# ltc.net
KiCad netlist of a schematic drawn in EAGLE
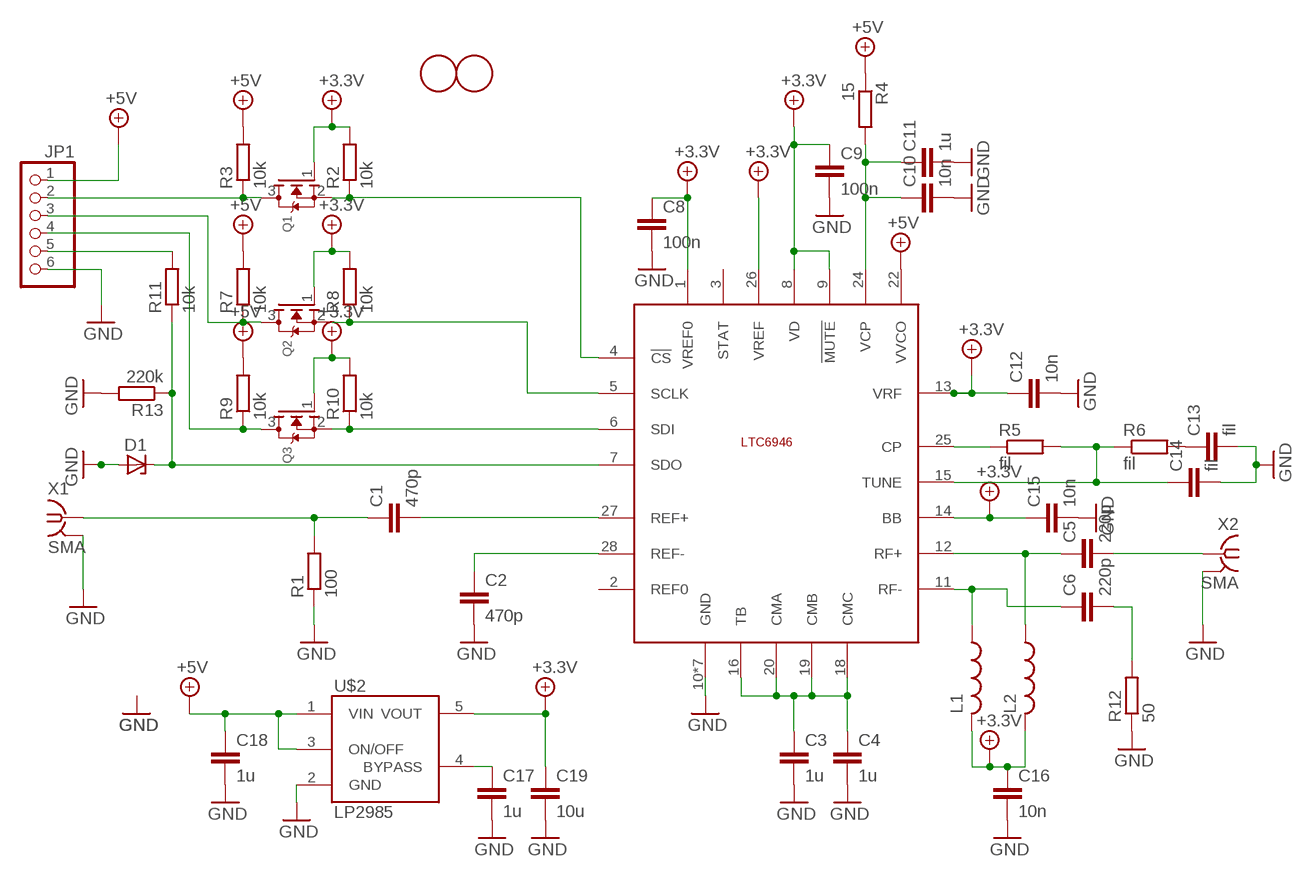
[diagram p0: schematic, sheet 1]

(export (version "E")
  (design (tool "Eeschema 10.0.6"))
  (components
    (comp (ref "C1")
      (value "470p")
      (footprint "eagle-import:C0603")
      (libsource (lib "eagle-import") (part "C-EUC0603"))
    )
    (comp (ref "C2")
      (value "470p")
      (footprint "eagle-import:C0603")
      (libsource (lib "eagle-import") (part "C-EUC0603"))
    )
    (comp (ref "C3")
      (value "1u")
      (footprint "eagle-import:C0603")
      (libsource (lib "eagle-import") (part "C-EUC0603"))
    )
    (comp (ref "C4")
      (value "1u")
      (footprint "eagle-import:C0603")
      (libsource (lib "eagle-import") (part "C-EUC0603"))
    )
    (comp (ref "C5")
      (value "220p")
      (footprint "eagle-import:C0603")
      (libsource (lib "eagle-import") (part "C-EUC0603"))
    )
    (comp (ref "C6")
      (value "220p")
      (footprint "eagle-import:C0603")
      (libsource (lib "eagle-import") (part "C-EUC0603"))
    )
    (comp (ref "C8")
      (value "100n")
      (footprint "eagle-import:C0603")
      (libsource (lib "eagle-import") (part "C-EUC0603"))
    )
    (comp (ref "C9")
      (value "100n")
      (footprint "eagle-import:C0603")
      (libsource (lib "eagle-import") (part "C-EUC0603"))
    )
    (comp (ref "C10")
      (value "10n")
      (footprint "eagle-import:C0603")
      (libsource (lib "eagle-import") (part "C-EUC0603"))
    )
    (comp (ref "C11")
      (value "1u")
      (footprint "eagle-import:C0603")
      (libsource (lib "eagle-import") (part "C-EUC0603"))
    )
    (comp (ref "C12")
      (value "10n")
      (footprint "eagle-import:C0603")
      (libsource (lib "eagle-import") (part "C-EUC0603"))
    )
    (comp (ref "C13")
      (value "fil")
      (footprint "eagle-import:C0603")
      (libsource (lib "eagle-import") (part "C-EUC0603"))
    )
    (comp (ref "C14")
      (value "fil")
      (footprint "eagle-import:C0603")
      (libsource (lib "eagle-import") (part "C-EUC0603"))
    )
    (comp (ref "C15")
      (value "10n")
      (footprint "eagle-import:C0603")
      (libsource (lib "eagle-import") (part "C-EUC0603"))
    )
    (comp (ref "C16")
      (value "10n")
      (footprint "eagle-import:C0603")
      (libsource (lib "eagle-import") (part "C-EUC0603"))
    )
    (comp (ref "C17")
      (value "1u")
      (footprint "eagle-import:C0603")
      (libsource (lib "eagle-import") (part "C-EUC0603"))
    )
    (comp (ref "C18")
      (value "1u")
      (footprint "eagle-import:C0603")
      (libsource (lib "eagle-import") (part "C-EUC0603"))
    )
    (comp (ref "C19")
      (value "10u")
      (footprint "eagle-import:C0603")
      (libsource (lib "eagle-import") (part "C-EUC0603"))
    )
    (comp (ref "D1")
      (value "ZENER-DIODESOT23")
      (footprint "eagle-import:SOT23")
      (libsource (lib "eagle-import") (part "ZENER-DIODESOT23"))
    )
    (comp (ref "JP1")
      (value "PINHD-1X6B")
      (footprint "eagle-import:1X06-BIG")
      (libsource (lib "eagle-import") (part "PINHD-1X6B"))
    )
    (comp (ref "L1")
      (value "L-USL2825P")
      (footprint "eagle-import:L2825P")
      (libsource (lib "eagle-import") (part "L-USL2825P"))
    )
    (comp (ref "L2")
      (value "L-USL2825P")
      (footprint "eagle-import:L2825P")
      (libsource (lib "eagle-import") (part "L-USL2825P"))
    )
    (comp (ref "Q1")
      (value "MOSFET-NREFLOW")
      (footprint "eagle-import:SOT23")
      (libsource (lib "eagle-import") (part "MOSFET-NREFLOW"))
    )
    (comp (ref "Q2")
      (value "MOSFET-NREFLOW")
      (footprint "eagle-import:SOT23")
      (libsource (lib "eagle-import") (part "MOSFET-NREFLOW"))
    )
    (comp (ref "Q3")
      (value "MOSFET-NREFLOW")
      (footprint "eagle-import:SOT23")
      (libsource (lib "eagle-import") (part "MOSFET-NREFLOW"))
    )
    (comp (ref "R1")
      (value "100")
      (footprint "eagle-import:R0603")
      (libsource (lib "eagle-import") (part "R-EU_R0603"))
    )
    (comp (ref "R2")
      (value "10k")
      (footprint "eagle-import:R0603")
      (libsource (lib "eagle-import") (part "R-EU_R0603"))
    )
    (comp (ref "R3")
      (value "10k")
      (footprint "eagle-import:R0603")
      (libsource (lib "eagle-import") (part "R-EU_R0603"))
    )
    (comp (ref "R4")
      (value "15")
      (footprint "eagle-import:R0603")
      (libsource (lib "eagle-import") (part "R-EU_R0603"))
    )
    (comp (ref "R5")
      (value "fil")
      (footprint "eagle-import:R0603")
      (libsource (lib "eagle-import") (part "R-EU_R0603"))
    )
    (comp (ref "R6")
      (value "fil")
      (footprint "eagle-import:R0603")
      (libsource (lib "eagle-import") (part "R-EU_R0603"))
    )
    (comp (ref "R7")
      (value "10k")
      (footprint "eagle-import:R0603")
      (libsource (lib "eagle-import") (part "R-EU_R0603"))
    )
    (comp (ref "R8")
      (value "10k")
      (footprint "eagle-import:R0603")
      (libsource (lib "eagle-import") (part "R-EU_R0603"))
    )
    (comp (ref "R9")
      (value "10k")
      (footprint "eagle-import:R0603")
      (libsource (lib "eagle-import") (part "R-EU_R0603"))
    )
    (comp (ref "R10")
      (value "10k")
      (footprint "eagle-import:R0603")
      (libsource (lib "eagle-import") (part "R-EU_R0603"))
    )
    (comp (ref "R11")
      (value "10k")
      (footprint "eagle-import:R0603")
      (libsource (lib "eagle-import") (part "R-EU_R0603"))
    )
    (comp (ref "R12")
      (value "50")
      (footprint "eagle-import:R0603")
      (libsource (lib "eagle-import") (part "R-EU_R0603"))
    )
    (comp (ref "R13")
      (value "220k")
      (footprint "eagle-import:R0603")
      (libsource (lib "eagle-import") (part "R-EU_R0603"))
    )
    (comp (ref "U$1")
      (value "LTC6946")
      (footprint "eagle-import:QFN28-UFD")
      (libsource (lib "eagle-import") (part "LTC6946"))
    )
    (comp (ref "U$2")
      (value "LP2985AIM5-3.3")
      (footprint "eagle-import:SOT25")
      (libsource (lib "eagle-import") (part "LP2985AIM5-3.3"))
    )
    (comp (ref "U$3")
      (value "FIDUCIAL")
      (footprint "eagle-import:FIDUCIAL_1MM")
      (libsource (lib "eagle-import") (part "FIDUCIAL"))
    )
    (comp (ref "U$4")
      (value "FIDUCIAL")
      (footprint "eagle-import:FIDUCIAL_1MM")
      (libsource (lib "eagle-import") (part "FIDUCIAL"))
    )
    (comp (ref "X1")
      (value "SMA")
      (footprint "eagle-import:J502-ND-142-0711-821_826")
      (fields (field (name "MF") "JOHNSON COMPONENTS") (field (name "MPN") "142-0711-821"))
      (libsource (lib "eagle-import") (part "SMA-142-0711-821/826"))
    )
    (comp (ref "X2")
      (value "SMA")
      (footprint "eagle-import:J502-ND-142-0711-821_826")
      (fields (field (name "MF") "JOHNSON COMPONENTS") (field (name "MPN") "142-0711-821"))
      (libsource (lib "eagle-import") (part "SMA-142-0711-821/826"))
    )
  )
  (nets
    (net (code "1") (name "+3.3V") (class "Default")
      (node (ref "C12") (pin "1") (pinfunction "1_1") (pintype "passive"))
      (node (ref "C15") (pin "1") (pinfunction "1_1") (pintype "passive"))
      (node (ref "C16") (pin "1") (pinfunction "1_1") (pintype "passive"))
      (node (ref "C19") (pin "1") (pinfunction "1_1") (pintype "passive"))
      (node (ref "C8") (pin "1") (pinfunction "1_1") (pintype "passive"))
      (node (ref "C9") (pin "1") (pinfunction "1_1") (pintype "passive"))
      (node (ref "L1") (pin "2") (pinfunction "2_2") (pintype "passive"))
      (node (ref "L2") (pin "2") (pinfunction "2_2") (pintype "passive"))
      (node (ref "Q1") (pin "1") (pinfunction "G_1") (pintype "bidirectional"))
      (node (ref "Q2") (pin "1") (pinfunction "G_1") (pintype "bidirectional"))
      (node (ref "Q3") (pin "1") (pinfunction "G_1") (pintype "bidirectional"))
      (node (ref "R10") (pin "2") (pinfunction "2_2") (pintype "passive"))
      (node (ref "R2") (pin "2") (pinfunction "2_2") (pintype "passive"))
      (node (ref "R8") (pin "2") (pinfunction "2_2") (pintype "passive"))
      (node (ref "U$1") (pin "1") (pinfunction "VREF0_1") (pintype "bidirectional"))
      (node (ref "U$1") (pin "13") (pinfunction "VRF_13") (pintype "bidirectional"))
      (node (ref "U$1") (pin "14") (pinfunction "BB_14") (pintype "bidirectional"))
      (node (ref "U$1") (pin "26") (pinfunction "VREF_26") (pintype "bidirectional"))
      (node (ref "U$1") (pin "8") (pinfunction "VD_8") (pintype "bidirectional"))
      (node (ref "U$1") (pin "9") (pinfunction "~{MUTE}_9") (pintype "bidirectional"))
      (node (ref "U$2") (pin "5") (pinfunction "VOUT_5") (pintype "power_in"))
    )
    (net (code "2") (name "+5V") (class "Default")
      (node (ref "C18") (pin "1") (pinfunction "1_1") (pintype "passive"))
      (node (ref "JP1") (pin "1") (pinfunction "1_1") (pintype "passive"))
      (node (ref "R3") (pin "2") (pinfunction "2_2") (pintype "passive"))
      (node (ref "R4") (pin "1") (pinfunction "1_1") (pintype "passive"))
      (node (ref "R7") (pin "2") (pinfunction "2_2") (pintype "passive"))
      (node (ref "R9") (pin "2") (pinfunction "2_2") (pintype "passive"))
      (node (ref "U$1") (pin "22") (pinfunction "VVCO_22") (pintype "bidirectional"))
      (node (ref "U$2") (pin "1") (pinfunction "VIN_1") (pintype "power_in"))
      (node (ref "U$2") (pin "3") (pinfunction "ON/OFF_3") (pintype "input"))
    )
    (net (code "3") (name "GND") (class "Default")
      (node (ref "C10") (pin "2") (pinfunction "2_2") (pintype "passive"))
      (node (ref "C11") (pin "2") (pinfunction "2_2") (pintype "passive"))
      (node (ref "C12") (pin "2") (pinfunction "2_2") (pintype "passive"))
      (node (ref "C13") (pin "2") (pinfunction "2_2") (pintype "passive"))
      (node (ref "C14") (pin "2") (pinfunction "2_2") (pintype "passive"))
      (node (ref "C15") (pin "2") (pinfunction "2_2") (pintype "passive"))
      (node (ref "C16") (pin "2") (pinfunction "2_2") (pintype "passive"))
      (node (ref "C17") (pin "2") (pinfunction "2_2") (pintype "passive"))
      (node (ref "C18") (pin "2") (pinfunction "2_2") (pintype "passive"))
      (node (ref "C19") (pin "2") (pinfunction "2_2") (pintype "passive"))
      (node (ref "C2") (pin "2") (pinfunction "2_2") (pintype "passive"))
      (node (ref "C3") (pin "2") (pinfunction "2_2") (pintype "passive"))
      (node (ref "C4") (pin "2") (pinfunction "2_2") (pintype "passive"))
      (node (ref "C8") (pin "2") (pinfunction "2_2") (pintype "passive"))
      (node (ref "C9") (pin "2") (pinfunction "2_2") (pintype "passive"))
      (node (ref "D1") (pin "1") (pinfunction "A_1") (pintype "passive"))
      (node (ref "JP1") (pin "6") (pinfunction "6_6") (pintype "passive"))
      (node (ref "R1") (pin "1") (pinfunction "1_1") (pintype "passive"))
      (node (ref "R12") (pin "1") (pinfunction "1_1") (pintype "passive"))
      (node (ref "R13") (pin "2") (pinfunction "2_2") (pintype "passive"))
      (node (ref "U$1") (pin "10") (pinfunction "GND_10") (pintype "bidirectional"))
      (node (ref "U$1") (pin "17") (pinfunction "GND_17") (pintype "bidirectional"))
      (node (ref "U$1") (pin "21") (pinfunction "GND_21") (pintype "bidirectional"))
      (node (ref "U$1") (pin "23") (pinfunction "GND_23") (pintype "bidirectional"))
      (node (ref "U$1") (pin "29") (pinfunction "GND_29") (pintype "bidirectional"))
      (node (ref "U$1") (pin "29@1") (pinfunction "GND_29@1") (pintype "bidirectional"))
      (node (ref "U$1") (pin "29@2") (pinfunction "GND_29@2") (pintype "bidirectional"))
      (node (ref "U$2") (pin "2") (pinfunction "GND_2") (pintype "power_in"))
      (node (ref "X1") (pin "G@1") (pinfunction "2_G@1") (pintype "passive"))
      (node (ref "X1") (pin "G@2") (pinfunction "2_G@2") (pintype "passive"))
      (node (ref "X1") (pin "G@3") (pinfunction "2_G@3") (pintype "passive"))
      (node (ref "X1") (pin "G@4") (pinfunction "2_G@4") (pintype "passive"))
      (node (ref "X2") (pin "G@1") (pinfunction "2_G@1") (pintype "passive"))
      (node (ref "X2") (pin "G@2") (pinfunction "2_G@2") (pintype "passive"))
      (node (ref "X2") (pin "G@3") (pinfunction "2_G@3") (pintype "passive"))
      (node (ref "X2") (pin "G@4") (pinfunction "2_G@4") (pintype "passive"))
    )
    (net (code "4") (name "Net-(C1-Pad1)") (class "Default")
      (node (ref "C1") (pin "1") (pinfunction "1_1") (pintype "passive"))
      (node (ref "R1") (pin "2") (pinfunction "2_2") (pintype "passive"))
      (node (ref "X1") (pin "1") (pinfunction "1_1") (pintype "passive"))
    )
    (net (code "5") (name "Net-(C5-Pad2)") (class "Default")
      (node (ref "C5") (pin "2") (pinfunction "2_2") (pintype "passive"))
      (node (ref "X2") (pin "1") (pinfunction "1_1") (pintype "passive"))
    )
    (net (code "6") (name "Net-(C6-Pad2)") (class "Default")
      (node (ref "C6") (pin "2") (pinfunction "2_2") (pintype "passive"))
      (node (ref "R12") (pin "2") (pinfunction "2_2") (pintype "passive"))
    )
    (net (code "7") (name "Net-(C13-Pad1)") (class "Default")
      (node (ref "C13") (pin "1") (pinfunction "1_1") (pintype "passive"))
      (node (ref "R6") (pin "2") (pinfunction "2_2") (pintype "passive"))
    )
    (net (code "8") (name "Net-(D1-C)") (class "Default")
      (node (ref "D1") (pin "3") (pinfunction "C_3") (pintype "passive"))
      (node (ref "R11") (pin "1") (pinfunction "1_1") (pintype "passive"))
      (node (ref "R13") (pin "1") (pinfunction "1_1") (pintype "passive"))
      (node (ref "U$1") (pin "7") (pinfunction "SDO_7") (pintype "bidirectional"))
    )
    (net (code "9") (name "Net-(JP1-Pad5)") (class "Default")
      (node (ref "JP1") (pin "5") (pinfunction "5_5") (pintype "passive"))
      (node (ref "R11") (pin "2") (pinfunction "2_2") (pintype "passive"))
    )
    (net (code "10") (name "Net-(Q1-D)") (class "Default")
      (node (ref "JP1") (pin "2") (pinfunction "2_2") (pintype "passive"))
      (node (ref "Q1") (pin "3") (pinfunction "D_3") (pintype "bidirectional"))
      (node (ref "R3") (pin "1") (pinfunction "1_1") (pintype "passive"))
    )
    (net (code "11") (name "Net-(Q1-S)") (class "Default")
      (node (ref "Q1") (pin "2") (pinfunction "S_2") (pintype "bidirectional"))
      (node (ref "R2") (pin "1") (pinfunction "1_1") (pintype "passive"))
      (node (ref "U$1") (pin "4") (pinfunction "~{CS}_4") (pintype "bidirectional"))
    )
    (net (code "12") (name "Net-(Q2-D)") (class "Default")
      (node (ref "JP1") (pin "3") (pinfunction "3_3") (pintype "passive"))
      (node (ref "Q2") (pin "3") (pinfunction "D_3") (pintype "bidirectional"))
      (node (ref "R7") (pin "1") (pinfunction "1_1") (pintype "passive"))
    )
    (net (code "13") (name "Net-(Q2-S)") (class "Default")
      (node (ref "Q2") (pin "2") (pinfunction "S_2") (pintype "bidirectional"))
      (node (ref "R8") (pin "1") (pinfunction "1_1") (pintype "passive"))
      (node (ref "U$1") (pin "5") (pinfunction "SCLK_5") (pintype "bidirectional"))
    )
    (net (code "14") (name "Net-(Q3-D)") (class "Default")
      (node (ref "JP1") (pin "4") (pinfunction "4_4") (pintype "passive"))
      (node (ref "Q3") (pin "3") (pinfunction "D_3") (pintype "bidirectional"))
      (node (ref "R9") (pin "1") (pinfunction "1_1") (pintype "passive"))
    )
    (net (code "15") (name "Net-(Q3-S)") (class "Default")
      (node (ref "Q3") (pin "2") (pinfunction "S_2") (pintype "bidirectional"))
      (node (ref "R10") (pin "1") (pinfunction "1_1") (pintype "passive"))
      (node (ref "U$1") (pin "6") (pinfunction "SDI_6") (pintype "bidirectional"))
    )
    (net (code "16") (name "Net-(U$1-CMA)") (class "Default")
      (node (ref "C3") (pin "1") (pinfunction "1_1") (pintype "passive"))
      (node (ref "C4") (pin "1") (pinfunction "1_1") (pintype "passive"))
      (node (ref "U$1") (pin "16") (pinfunction "TB_16") (pintype "bidirectional"))
      (node (ref "U$1") (pin "18") (pinfunction "CMC_18") (pintype "bidirectional"))
      (node (ref "U$1") (pin "19") (pinfunction "CMB_19") (pintype "bidirectional"))
      (node (ref "U$1") (pin "20") (pinfunction "CMA_20") (pintype "bidirectional"))
    )
    (net (code "17") (name "Net-(U$1-CP)") (class "Default")
      (node (ref "R5") (pin "1") (pinfunction "1_1") (pintype "passive"))
      (node (ref "U$1") (pin "25") (pinfunction "CP_25") (pintype "bidirectional"))
    )
    (net (code "18") (name "Net-(U$1-REF+)") (class "Default")
      (node (ref "C1") (pin "2") (pinfunction "2_2") (pintype "passive"))
      (node (ref "U$1") (pin "27") (pinfunction "REF+_27") (pintype "bidirectional"))
    )
    (net (code "19") (name "Net-(U$1-REF-)") (class "Default")
      (node (ref "C2") (pin "1") (pinfunction "1_1") (pintype "passive"))
      (node (ref "U$1") (pin "28") (pinfunction "REF-_28") (pintype "bidirectional"))
    )
    (net (code "20") (name "Net-(U$1-RF+)") (class "Default")
      (node (ref "C5") (pin "1") (pinfunction "1_1") (pintype "passive"))
      (node (ref "L2") (pin "1") (pinfunction "1_1") (pintype "passive"))
      (node (ref "U$1") (pin "12") (pinfunction "RF+_12") (pintype "bidirectional"))
    )
    (net (code "21") (name "Net-(U$1-RF-)") (class "Default")
      (node (ref "C6") (pin "1") (pinfunction "1_1") (pintype "passive"))
      (node (ref "L1") (pin "1") (pinfunction "1_1") (pintype "passive"))
      (node (ref "U$1") (pin "11") (pinfunction "RF-_11") (pintype "bidirectional"))
    )
    (net (code "22") (name "Net-(U$1-TUNE)") (class "Default")
      (node (ref "C14") (pin "1") (pinfunction "1_1") (pintype "passive"))
      (node (ref "R5") (pin "2") (pinfunction "2_2") (pintype "passive"))
      (node (ref "R6") (pin "1") (pinfunction "1_1") (pintype "passive"))
      (node (ref "U$1") (pin "15") (pinfunction "TUNE_15") (pintype "bidirectional"))
    )
    (net (code "23") (name "Net-(U$1-VCP)") (class "Default")
      (node (ref "C10") (pin "1") (pinfunction "1_1") (pintype "passive"))
      (node (ref "C11") (pin "1") (pinfunction "1_1") (pintype "passive"))
      (node (ref "R4") (pin "2") (pinfunction "2_2") (pintype "passive"))
      (node (ref "U$1") (pin "24") (pinfunction "VCP_24") (pintype "bidirectional"))
    )
    (net (code "24") (name "Net-(U$2-BYPASS)") (class "Default")
      (node (ref "C17") (pin "1") (pinfunction "1_1") (pintype "passive"))
      (node (ref "U$2") (pin "4") (pinfunction "BYPASS_4") (pintype "power_in"))
    )
    (net (code "25") (name "unconnected-(U$1-REF0-Pad2)") (class "Default")
      (node (ref "U$1") (pin "2") (pinfunction "REF0_2") (pintype "bidirectional"))
    )
    (net (code "26") (name "unconnected-(U$1-STAT-Pad3)") (class "Default")
      (node (ref "U$1") (pin "3") (pinfunction "STAT_3") (pintype "bidirectional"))
    )
  )
)
